# controlador.net
KiCad netlist of a schematic drawn in EAGLE
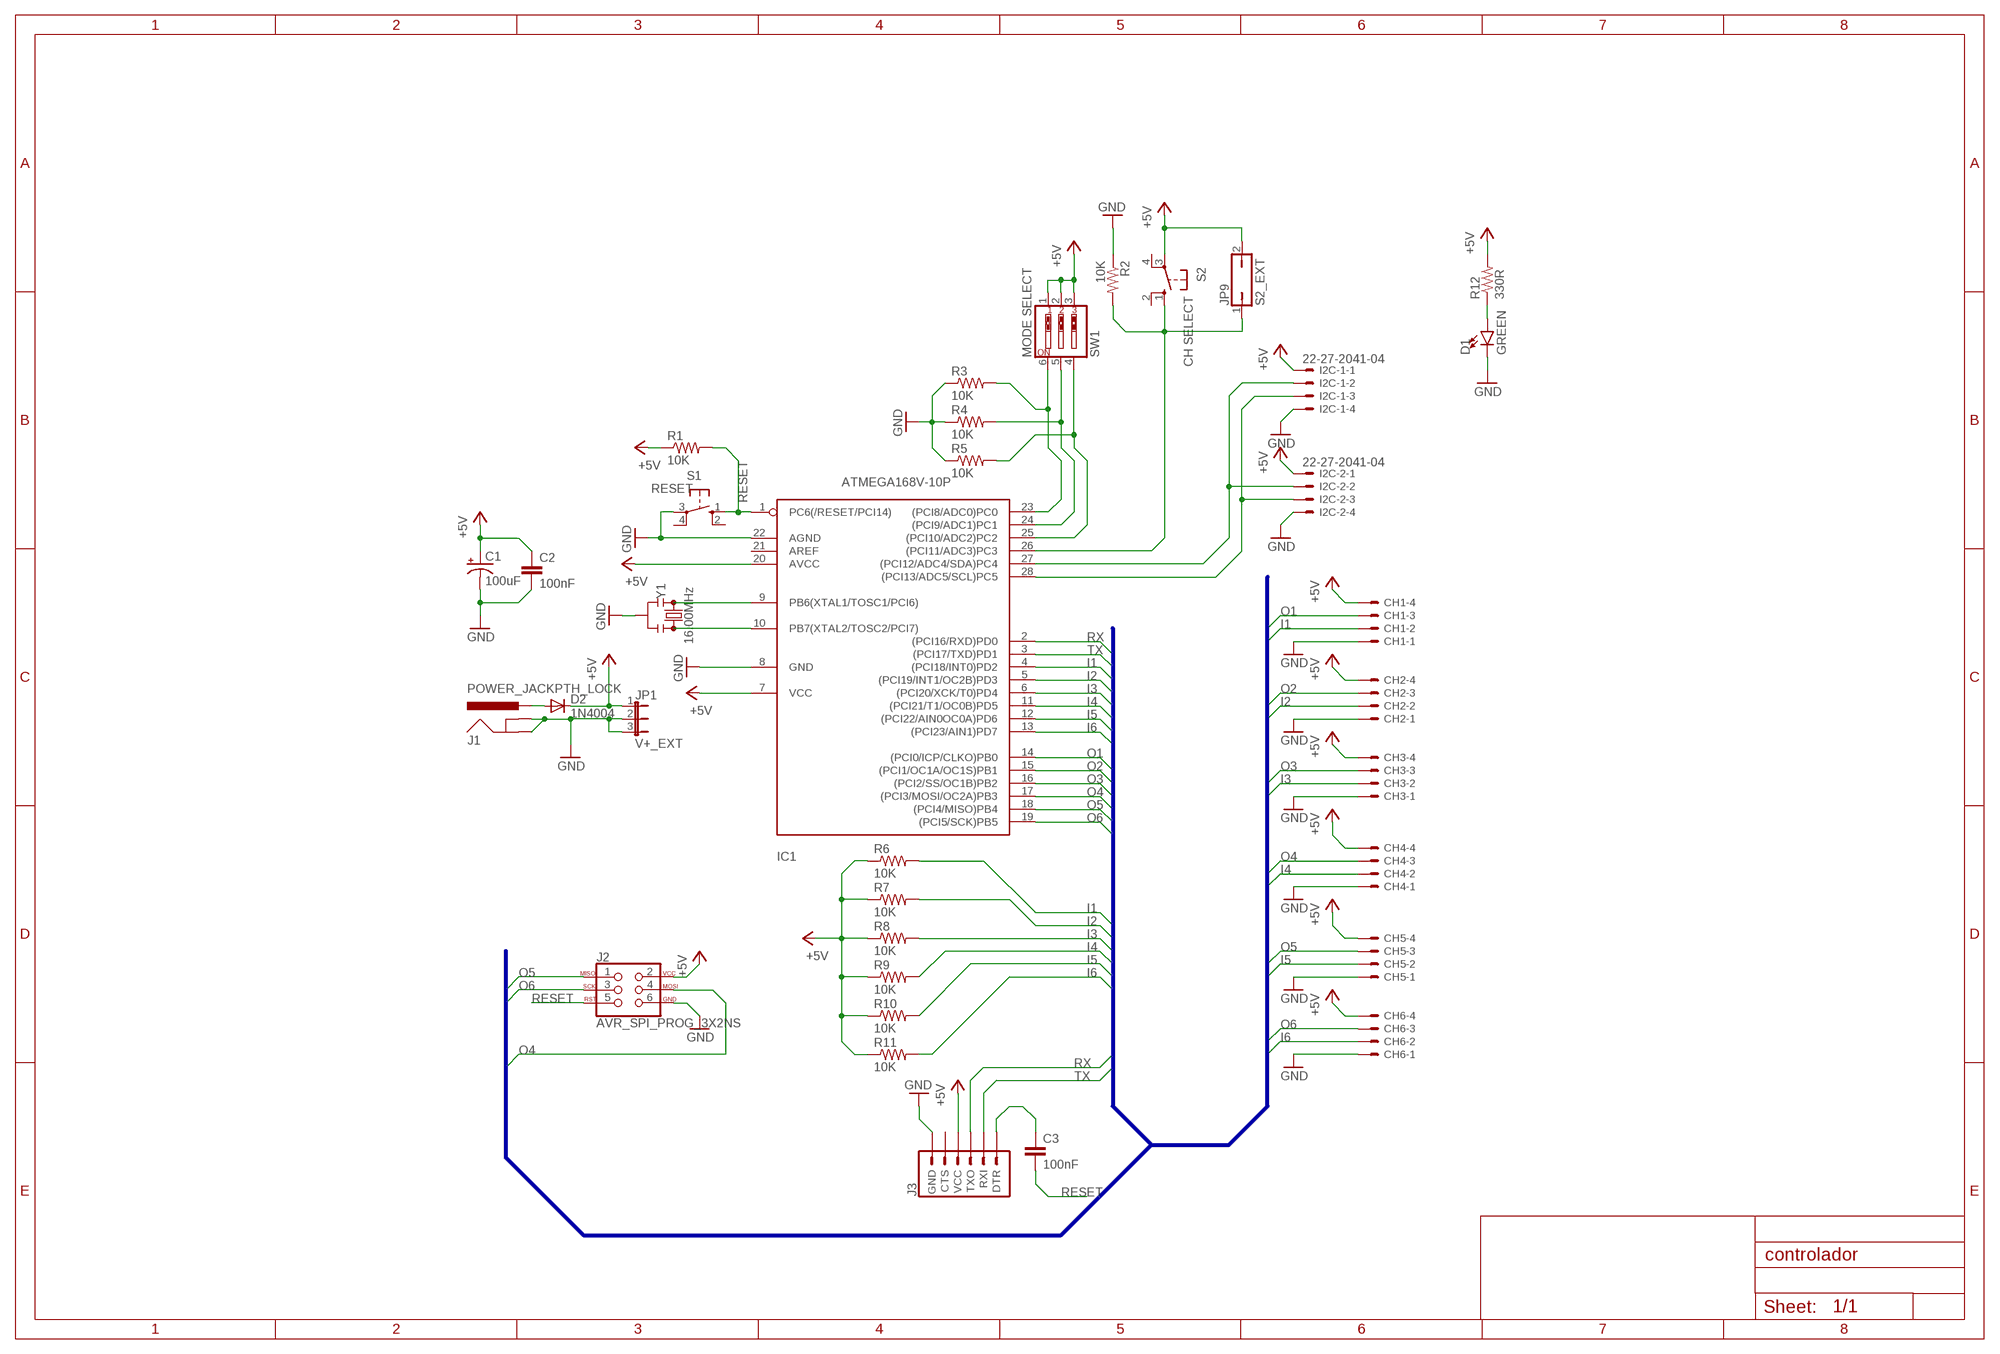
[diagram p0: schematic, sheet 1]

(export (version "E")
  (design (tool "Eeschema 10.0.6"))
  (components
    (comp (ref "C1")
      (value "100uF")
      (footprint "eagle-import:E2,5-7")
      (libsource (lib "eagle-import") (part "CPOL-USE2.5-7"))
    )
    (comp (ref "C2")
      (value "100nF")
      (footprint "eagle-import:C075-032X103")
      (libsource (lib "eagle-import") (part "C-EU075-032X103"))
    )
    (comp (ref "C3")
      (value "100nF")
      (footprint "eagle-import:C075-032X103")
      (libsource (lib "eagle-import") (part "C-EU075-032X103"))
    )
    (comp (ref "CH1")
      (value "22-27-2041-04")
      (footprint "eagle-import:6410-04")
      (libsource (lib "eagle-import") (part "22-?-0427-2041"))
    )
    (comp (ref "CH2")
      (value "22-27-2041-04")
      (footprint "eagle-import:6410-04")
      (libsource (lib "eagle-import") (part "22-?-0427-2041"))
    )
    (comp (ref "CH3")
      (value "22-27-2041-04")
      (footprint "eagle-import:6410-04")
      (libsource (lib "eagle-import") (part "22-?-0427-2041"))
    )
    (comp (ref "CH4")
      (value "22-27-2041-04")
      (footprint "eagle-import:6410-04")
      (libsource (lib "eagle-import") (part "22-?-0427-2041"))
    )
    (comp (ref "CH5")
      (value "22-27-2041-04")
      (footprint "eagle-import:6410-04")
      (libsource (lib "eagle-import") (part "22-?-0427-2041"))
    )
    (comp (ref "CH6")
      (value "22-27-2041-04")
      (footprint "eagle-import:6410-04")
      (libsource (lib "eagle-import") (part "22-?-0427-2041"))
    )
    (comp (ref "D1")
      (value "GREEN")
      (footprint "eagle-import:LED_5MM")
      (libsource (lib "eagle-import") (part "LED5MM"))
    )
    (comp (ref "D2")
      (value "1N4004")
      (footprint "eagle-import:DO41-10")
      (libsource (lib "eagle-import") (part "1N4004"))
    )
    (comp (ref "I2C-1")
      (value "22-27-2041-04")
      (footprint "eagle-import:6410-04")
      (libsource (lib "eagle-import") (part "22-?-0427-2041"))
    )
    (comp (ref "I2C-2")
      (value "22-27-2041-04")
      (footprint "eagle-import:6410-04")
      (libsource (lib "eagle-import") (part "22-?-0427-2041"))
    )
    (comp (ref "IC1")
      (value "ATMEGA168V-10P")
      (footprint "eagle-import:DIL28-3")
      (libsource (lib "eagle-import") (part "ATMEGA168PV-10"))
    )
    (comp (ref "J1")
      (value "POWER_JACKPTH_LOCK")
      (footprint "eagle-import:POWER_JACK_PTH_LOCK")
      (libsource (lib "eagle-import") (part "POWER_JACKPTH_LOCK"))
    )
    (comp (ref "J2")
      (value "AVR_SPI_PROG_3X2NS")
      (footprint "eagle-import:2X3-NS")
      (libsource (lib "eagle-import") (part "AVR_SPI_PROG_3X2NS"))
    )
    (comp (ref "J3")
      (value "6_PIN_SERIAL_TARGETSILK")
      (footprint "eagle-import:6_PIN_SERIAL_TARGET_SIDE_W_SILK")
      (libsource (lib "eagle-import") (part "6_PIN_SERIAL_TARGETSILK"))
    )
    (comp (ref "JP1")
      (value "V+_EXT")
      (footprint "eagle-import:JP2")
      (libsource (lib "eagle-import") (part "JP2E"))
    )
    (comp (ref "JP9")
      (value "S2_EXT")
      (footprint "eagle-import:JP1")
      (libsource (lib "eagle-import") (part "JP1Q"))
    )
    (comp (ref "R1")
      (value "10K")
      (footprint "eagle-import:0204_7")
      (libsource (lib "eagle-import") (part "R-US_0204/7"))
    )
    (comp (ref "R2")
      (value "10K")
      (footprint "eagle-import:0204_7")
      (libsource (lib "eagle-import") (part "R-US_0204/7"))
    )
    (comp (ref "R3")
      (value "10K")
      (footprint "eagle-import:0204_7")
      (libsource (lib "eagle-import") (part "R-US_0204/7"))
    )
    (comp (ref "R4")
      (value "10K")
      (footprint "eagle-import:0204_7")
      (libsource (lib "eagle-import") (part "R-US_0204/7"))
    )
    (comp (ref "R5")
      (value "10K")
      (footprint "eagle-import:0204_7")
      (libsource (lib "eagle-import") (part "R-US_0204/7"))
    )
    (comp (ref "R6")
      (value "10K")
      (footprint "eagle-import:0204_7")
      (libsource (lib "eagle-import") (part "R-US_0204/7"))
    )
    (comp (ref "R7")
      (value "10K")
      (footprint "eagle-import:0204_7")
      (libsource (lib "eagle-import") (part "R-US_0204/7"))
    )
    (comp (ref "R8")
      (value "10K")
      (footprint "eagle-import:0204_7")
      (libsource (lib "eagle-import") (part "R-US_0204/7"))
    )
    (comp (ref "R9")
      (value "10K")
      (footprint "eagle-import:0204_7")
      (libsource (lib "eagle-import") (part "R-US_0204/7"))
    )
    (comp (ref "R10")
      (value "10K")
      (footprint "eagle-import:0204_7")
      (libsource (lib "eagle-import") (part "R-US_0204/7"))
    )
    (comp (ref "R11")
      (value "10K")
      (footprint "eagle-import:0204_7")
      (libsource (lib "eagle-import") (part "R-US_0204/7"))
    )
    (comp (ref "R12")
      (value "330R")
      (footprint "eagle-import:0204_7")
      (libsource (lib "eagle-import") (part "resistor_R-US_0204/7"))
    )
    (comp (ref "S1")
      (value "RESET")
      (footprint "eagle-import:B3F-10XX")
      (fields (field (name "MPN") "B3F-1000"))
      (libsource (lib "eagle-import") (part "10-XX"))
    )
    (comp (ref "S2")
      (value "CH SELECT")
      (footprint "eagle-import:B3F-10XX")
      (fields (field (name "MPN") "B3F-1000"))
      (libsource (lib "eagle-import") (part "10-XX"))
    )
    (comp (ref "SW1")
      (value "MODE SELECT")
      (footprint "eagle-import:EDG-03")
      (libsource (lib "eagle-import") (part "SW_DIP-3"))
    )
    (comp (ref "Y1")
      (value "16.00MHz")
      (footprint "eagle-import:RESONATOR-PTH-7.6X3.8")
      (libsource (lib "eagle-import") (part "RESONATORPTH-7.6X3.8"))
    )
  )
  (nets
    (net (code "1") (name "+5V") (class "Default")
      (node (ref "C1") (pin "+") (pinfunction "+_+") (pintype "passive"))
      (node (ref "C2") (pin "1") (pinfunction "1_1") (pintype "passive"))
      (node (ref "CH1") (pin "4") (pinfunction "S_4") (pintype "passive"))
      (node (ref "CH2") (pin "4") (pinfunction "S_4") (pintype "passive"))
      (node (ref "CH3") (pin "4") (pinfunction "S_4") (pintype "passive"))
      (node (ref "CH4") (pin "4") (pinfunction "S_4") (pintype "passive"))
      (node (ref "CH5") (pin "4") (pinfunction "S_4") (pintype "passive"))
      (node (ref "CH6") (pin "4") (pinfunction "S_4") (pintype "passive"))
      (node (ref "D2") (pin "C") (pinfunction "C_C") (pintype "passive"))
      (node (ref "I2C-1") (pin "1") (pinfunction "S_1") (pintype "passive"))
      (node (ref "I2C-2") (pin "1") (pinfunction "S_1") (pintype "passive"))
      (node (ref "IC1") (pin "20") (pinfunction "AVCC_20") (pintype "bidirectional"))
      (node (ref "IC1") (pin "7") (pinfunction "VCC_7") (pintype "bidirectional"))
      (node (ref "J2") (pin "2") (pinfunction "2_2") (pintype "passive"))
      (node (ref "J3") (pin "P$4") (pinfunction "VCC_P$4") (pintype "passive"))
      (node (ref "JP1") (pin "1") (pinfunction "1_1") (pintype "passive"))
      (node (ref "JP9") (pin "2") (pinfunction "2_2") (pintype "passive"))
      (node (ref "R1") (pin "1") (pinfunction "1_1") (pintype "passive"))
      (node (ref "R10") (pin "1") (pinfunction "1_1") (pintype "passive"))
      (node (ref "R11") (pin "1") (pinfunction "1_1") (pintype "passive"))
      (node (ref "R12") (pin "2") (pinfunction "2_2") (pintype "passive"))
      (node (ref "R6") (pin "1") (pinfunction "1_1") (pintype "passive"))
      (node (ref "R7") (pin "1") (pinfunction "1_1") (pintype "passive"))
      (node (ref "R8") (pin "1") (pinfunction "1_1") (pintype "passive"))
      (node (ref "R9") (pin "1") (pinfunction "1_1") (pintype "passive"))
      (node (ref "S2") (pin "3") (pinfunction "P_3") (pintype "passive"))
      (node (ref "SW1") (pin "1") (pinfunction "1_1") (pintype "passive"))
      (node (ref "SW1") (pin "2") (pinfunction "2_2") (pintype "passive"))
      (node (ref "SW1") (pin "3") (pinfunction "3_3") (pintype "passive"))
    )
    (net (code "2") (name "/I1") (class "Default")
      (node (ref "CH1") (pin "2") (pinfunction "S_2") (pintype "passive"))
      (node (ref "IC1") (pin "4") (pinfunction "(PCI18/INT0)PD2_4") (pintype "bidirectional"))
      (node (ref "R6") (pin "2") (pinfunction "2_2") (pintype "passive"))
    )
    (net (code "3") (name "/I2") (class "Default")
      (node (ref "CH2") (pin "2") (pinfunction "S_2") (pintype "passive"))
      (node (ref "IC1") (pin "5") (pinfunction "(PCI19/INT1/OC2B)PD3_5") (pintype "bidirectional"))
      (node (ref "R7") (pin "2") (pinfunction "2_2") (pintype "passive"))
    )
    (net (code "4") (name "/I3") (class "Default")
      (node (ref "CH3") (pin "2") (pinfunction "S_2") (pintype "passive"))
      (node (ref "IC1") (pin "6") (pinfunction "(PCI20/XCK/T0)PD4_6") (pintype "bidirectional"))
      (node (ref "R8") (pin "2") (pinfunction "2_2") (pintype "passive"))
    )
    (net (code "5") (name "/I4") (class "Default")
      (node (ref "CH4") (pin "2") (pinfunction "S_2") (pintype "passive"))
      (node (ref "IC1") (pin "11") (pinfunction "(PCI21/T1/OC0B)PD5_11") (pintype "bidirectional"))
      (node (ref "R9") (pin "2") (pinfunction "2_2") (pintype "passive"))
    )
    (net (code "6") (name "/I5") (class "Default")
      (node (ref "CH5") (pin "2") (pinfunction "S_2") (pintype "passive"))
      (node (ref "IC1") (pin "12") (pinfunction "(PCI22/AIN0OC0A)PD6_12") (pintype "bidirectional"))
      (node (ref "R10") (pin "2") (pinfunction "2_2") (pintype "passive"))
    )
    (net (code "7") (name "/I6") (class "Default")
      (node (ref "CH6") (pin "2") (pinfunction "S_2") (pintype "passive"))
      (node (ref "IC1") (pin "13") (pinfunction "(PCI23/AIN1)PD7_13") (pintype "bidirectional"))
      (node (ref "R11") (pin "2") (pinfunction "2_2") (pintype "passive"))
    )
    (net (code "8") (name "/O1") (class "Default")
      (node (ref "CH1") (pin "3") (pinfunction "S_3") (pintype "passive"))
      (node (ref "IC1") (pin "14") (pinfunction "(PCI0/ICP/CLKO)PB0_14") (pintype "bidirectional"))
    )
    (net (code "9") (name "/O2") (class "Default")
      (node (ref "CH2") (pin "3") (pinfunction "S_3") (pintype "passive"))
      (node (ref "IC1") (pin "15") (pinfunction "(PCI1/OC1A/OC1S)PB1_15") (pintype "bidirectional"))
    )
    (net (code "10") (name "/O3") (class "Default")
      (node (ref "CH3") (pin "3") (pinfunction "S_3") (pintype "passive"))
      (node (ref "IC1") (pin "16") (pinfunction "(PCI2/SS/OC1B)PB2_16") (pintype "bidirectional"))
    )
    (net (code "11") (name "/O4") (class "Default")
      (node (ref "CH4") (pin "3") (pinfunction "S_3") (pintype "passive"))
      (node (ref "IC1") (pin "17") (pinfunction "(PCI3/MOSI/OC2A)PB3_17") (pintype "bidirectional"))
      (node (ref "J2") (pin "4") (pinfunction "4_4") (pintype "passive"))
    )
    (net (code "12") (name "/O5") (class "Default")
      (node (ref "CH5") (pin "3") (pinfunction "S_3") (pintype "passive"))
      (node (ref "IC1") (pin "18") (pinfunction "(PCI4/MISO)PB4_18") (pintype "bidirectional"))
      (node (ref "J2") (pin "1") (pinfunction "1_1") (pintype "passive"))
    )
    (net (code "13") (name "/O6") (class "Default")
      (node (ref "CH6") (pin "3") (pinfunction "S_3") (pintype "passive"))
      (node (ref "IC1") (pin "19") (pinfunction "(PCI5/SCK)PB5_19") (pintype "bidirectional"))
      (node (ref "J2") (pin "3") (pinfunction "3_3") (pintype "passive"))
    )
    (net (code "14") (name "/RESET") (class "Default")
      (node (ref "C3") (pin "2") (pinfunction "2_2") (pintype "passive"))
      (node (ref "IC1") (pin "1") (pinfunction "PC6(/RESET/PCI14)_1") (pintype "bidirectional"))
      (node (ref "J2") (pin "5") (pinfunction "5_5") (pintype "passive"))
      (node (ref "R1") (pin "2") (pinfunction "2_2") (pintype "passive"))
      (node (ref "S1") (pin "1") (pinfunction "S_1") (pintype "passive"))
    )
    (net (code "15") (name "/RX") (class "Default")
      (node (ref "IC1") (pin "2") (pinfunction "(PCI16/RXD)PD0_2") (pintype "bidirectional"))
      (node (ref "J3") (pin "P$2") (pinfunction "TXO_P$2") (pintype "passive"))
    )
    (net (code "16") (name "/TX") (class "Default")
      (node (ref "IC1") (pin "3") (pinfunction "(PCI17/TXD)PD1_3") (pintype "bidirectional"))
      (node (ref "J3") (pin "P$3") (pinfunction "RXI_P$3") (pintype "passive"))
    )
    (net (code "17") (name "GND") (class "Default")
      (node (ref "C1") (pin "-") (pinfunction "-_-") (pintype "passive"))
      (node (ref "C2") (pin "2") (pinfunction "2_2") (pintype "passive"))
      (node (ref "CH1") (pin "1") (pinfunction "S_1") (pintype "passive"))
      (node (ref "CH2") (pin "1") (pinfunction "S_1") (pintype "passive"))
      (node (ref "CH3") (pin "1") (pinfunction "S_1") (pintype "passive"))
      (node (ref "CH4") (pin "1") (pinfunction "S_1") (pintype "passive"))
      (node (ref "CH5") (pin "1") (pinfunction "S_1") (pintype "passive"))
      (node (ref "CH6") (pin "1") (pinfunction "S_1") (pintype "passive"))
      (node (ref "D1") (pin "K") (pinfunction "C_K") (pintype "passive"))
      (node (ref "I2C-1") (pin "4") (pinfunction "S_4") (pintype "passive"))
      (node (ref "I2C-2") (pin "4") (pinfunction "S_4") (pintype "passive"))
      (node (ref "IC1") (pin "22") (pinfunction "AGND_22") (pintype "bidirectional"))
      (node (ref "IC1") (pin "8") (pinfunction "GND_8") (pintype "bidirectional"))
      (node (ref "J1") (pin "GND") (pinfunction "GND_GND") (pintype "bidirectional"))
      (node (ref "J1") (pin "GNDBREAK") (pinfunction "GNDBREAK_GNDBREAK") (pintype "bidirectional"))
      (node (ref "J2") (pin "6") (pinfunction "6_6") (pintype "passive"))
      (node (ref "J3") (pin "P$6") (pinfunction "GND_P$6") (pintype "passive"))
      (node (ref "JP1") (pin "2") (pinfunction "2_2") (pintype "passive"))
      (node (ref "JP1") (pin "3") (pinfunction "3_3") (pintype "passive"))
      (node (ref "R2") (pin "1") (pinfunction "1_1") (pintype "passive"))
      (node (ref "R3") (pin "1") (pinfunction "1_1") (pintype "passive"))
      (node (ref "R4") (pin "1") (pinfunction "1_1") (pintype "passive"))
      (node (ref "R5") (pin "1") (pinfunction "1_1") (pintype "passive"))
      (node (ref "S1") (pin "3") (pinfunction "P_3") (pintype "passive"))
      (node (ref "Y1") (pin "2") (pinfunction "2_2") (pintype "passive"))
    )
    (net (code "18") (name "Net-(D1-PadA)") (class "Default")
      (node (ref "D1") (pin "A") (pinfunction "A_A") (pintype "passive"))
      (node (ref "R12") (pin "1") (pinfunction "1_1") (pintype "passive"))
    )
    (net (code "19") (name "Net-(D2-PadA)") (class "Default")
      (node (ref "D2") (pin "A") (pinfunction "A_A") (pintype "passive"))
      (node (ref "J1") (pin "PWR") (pinfunction "PWR_PWR") (pintype "bidirectional"))
    )
    (net (code "20") (name "Net-(I2C-1B-S)") (class "Default")
      (node (ref "I2C-1") (pin "2") (pinfunction "S_2") (pintype "passive"))
      (node (ref "I2C-2") (pin "2") (pinfunction "S_2") (pintype "passive"))
      (node (ref "IC1") (pin "27") (pinfunction "(PCI12/ADC4/SDA)PC4_27") (pintype "bidirectional"))
    )
    (net (code "21") (name "Net-(I2C-1C-S)") (class "Default")
      (node (ref "I2C-1") (pin "3") (pinfunction "S_3") (pintype "passive"))
      (node (ref "I2C-2") (pin "3") (pinfunction "S_3") (pintype "passive"))
      (node (ref "IC1") (pin "28") (pinfunction "(PCI13/ADC5/SCL)PC5_28") (pintype "bidirectional"))
    )
    (net (code "22") (name "Net-(IC1-(PCI8{slash}ADC0)PC0)") (class "Default")
      (node (ref "IC1") (pin "23") (pinfunction "(PCI8/ADC0)PC0_23") (pintype "bidirectional"))
      (node (ref "R3") (pin "2") (pinfunction "2_2") (pintype "passive"))
      (node (ref "SW1") (pin "6") (pinfunction "6_6") (pintype "passive"))
    )
    (net (code "23") (name "Net-(IC1-(PCI9{slash}ADC1)PC1)") (class "Default")
      (node (ref "IC1") (pin "24") (pinfunction "(PCI9/ADC1)PC1_24") (pintype "bidirectional"))
      (node (ref "R4") (pin "2") (pinfunction "2_2") (pintype "passive"))
      (node (ref "SW1") (pin "5") (pinfunction "5_5") (pintype "passive"))
    )
    (net (code "24") (name "Net-(IC1-(PCI10{slash}ADC2)PC2)") (class "Default")
      (node (ref "IC1") (pin "25") (pinfunction "(PCI10/ADC2)PC2_25") (pintype "bidirectional"))
      (node (ref "R5") (pin "2") (pinfunction "2_2") (pintype "passive"))
      (node (ref "SW1") (pin "4") (pinfunction "4_4") (pintype "passive"))
    )
    (net (code "25") (name "Net-(IC1-(PCI11{slash}ADC3)PC3)") (class "Default")
      (node (ref "IC1") (pin "26") (pinfunction "(PCI11/ADC3)PC3_26") (pintype "bidirectional"))
      (node (ref "JP9") (pin "1") (pinfunction "1_1") (pintype "passive"))
      (node (ref "R2") (pin "2") (pinfunction "2_2") (pintype "passive"))
      (node (ref "S2") (pin "1") (pinfunction "S_1") (pintype "passive"))
    )
    (net (code "26") (name "Net-(IC1-PB6(XTAL1{slash}TOSC1{slash}PCI6))") (class "Default")
      (node (ref "IC1") (pin "9") (pinfunction "PB6(XTAL1/TOSC1/PCI6)_9") (pintype "bidirectional"))
      (node (ref "Y1") (pin "1") (pinfunction "1_1") (pintype "passive"))
    )
    (net (code "27") (name "Net-(IC1-PB7(XTAL2{slash}TOSC2{slash}PCI7))") (class "Default")
      (node (ref "IC1") (pin "10") (pinfunction "PB7(XTAL2/TOSC2/PCI7)_10") (pintype "bidirectional"))
      (node (ref "Y1") (pin "3") (pinfunction "3_3") (pintype "passive"))
    )
    (net (code "28") (name "Net-(J3-DTR)") (class "Default")
      (node (ref "C3") (pin "1") (pinfunction "1_1") (pintype "passive"))
      (node (ref "J3") (pin "P$1") (pinfunction "DTR_P$1") (pintype "passive"))
    )
    (net (code "29") (name "unconnected-(IC1-AREF-Pad21)") (class "Default")
      (node (ref "IC1") (pin "21") (pinfunction "AREF_21") (pintype "bidirectional"))
    )
    (net (code "30") (name "unconnected-(J3-CTS-PadP$5)") (class "Default")
      (node (ref "J3") (pin "P$5") (pinfunction "CTS_P$5") (pintype "passive"))
    )
    (net (code "31") (name "unconnected-(S1-P1-Pad4)") (class "Default")
      (node (ref "S1") (pin "4") (pinfunction "P1_4") (pintype "passive"))
    )
    (net (code "32") (name "unconnected-(S1-S1-Pad2)") (class "Default")
      (node (ref "S1") (pin "2") (pinfunction "S1_2") (pintype "passive"))
    )
    (net (code "33") (name "unconnected-(S2-P1-Pad4)") (class "Default")
      (node (ref "S2") (pin "4") (pinfunction "P1_4") (pintype "passive"))
    )
    (net (code "34") (name "unconnected-(S2-S1-Pad2)") (class "Default")
      (node (ref "S2") (pin "2") (pinfunction "S1_2") (pintype "passive"))
    )
  )
)
